# HUM-ASM-001-v0-1.net
KiCad netlist of a schematic drawn in EAGLE
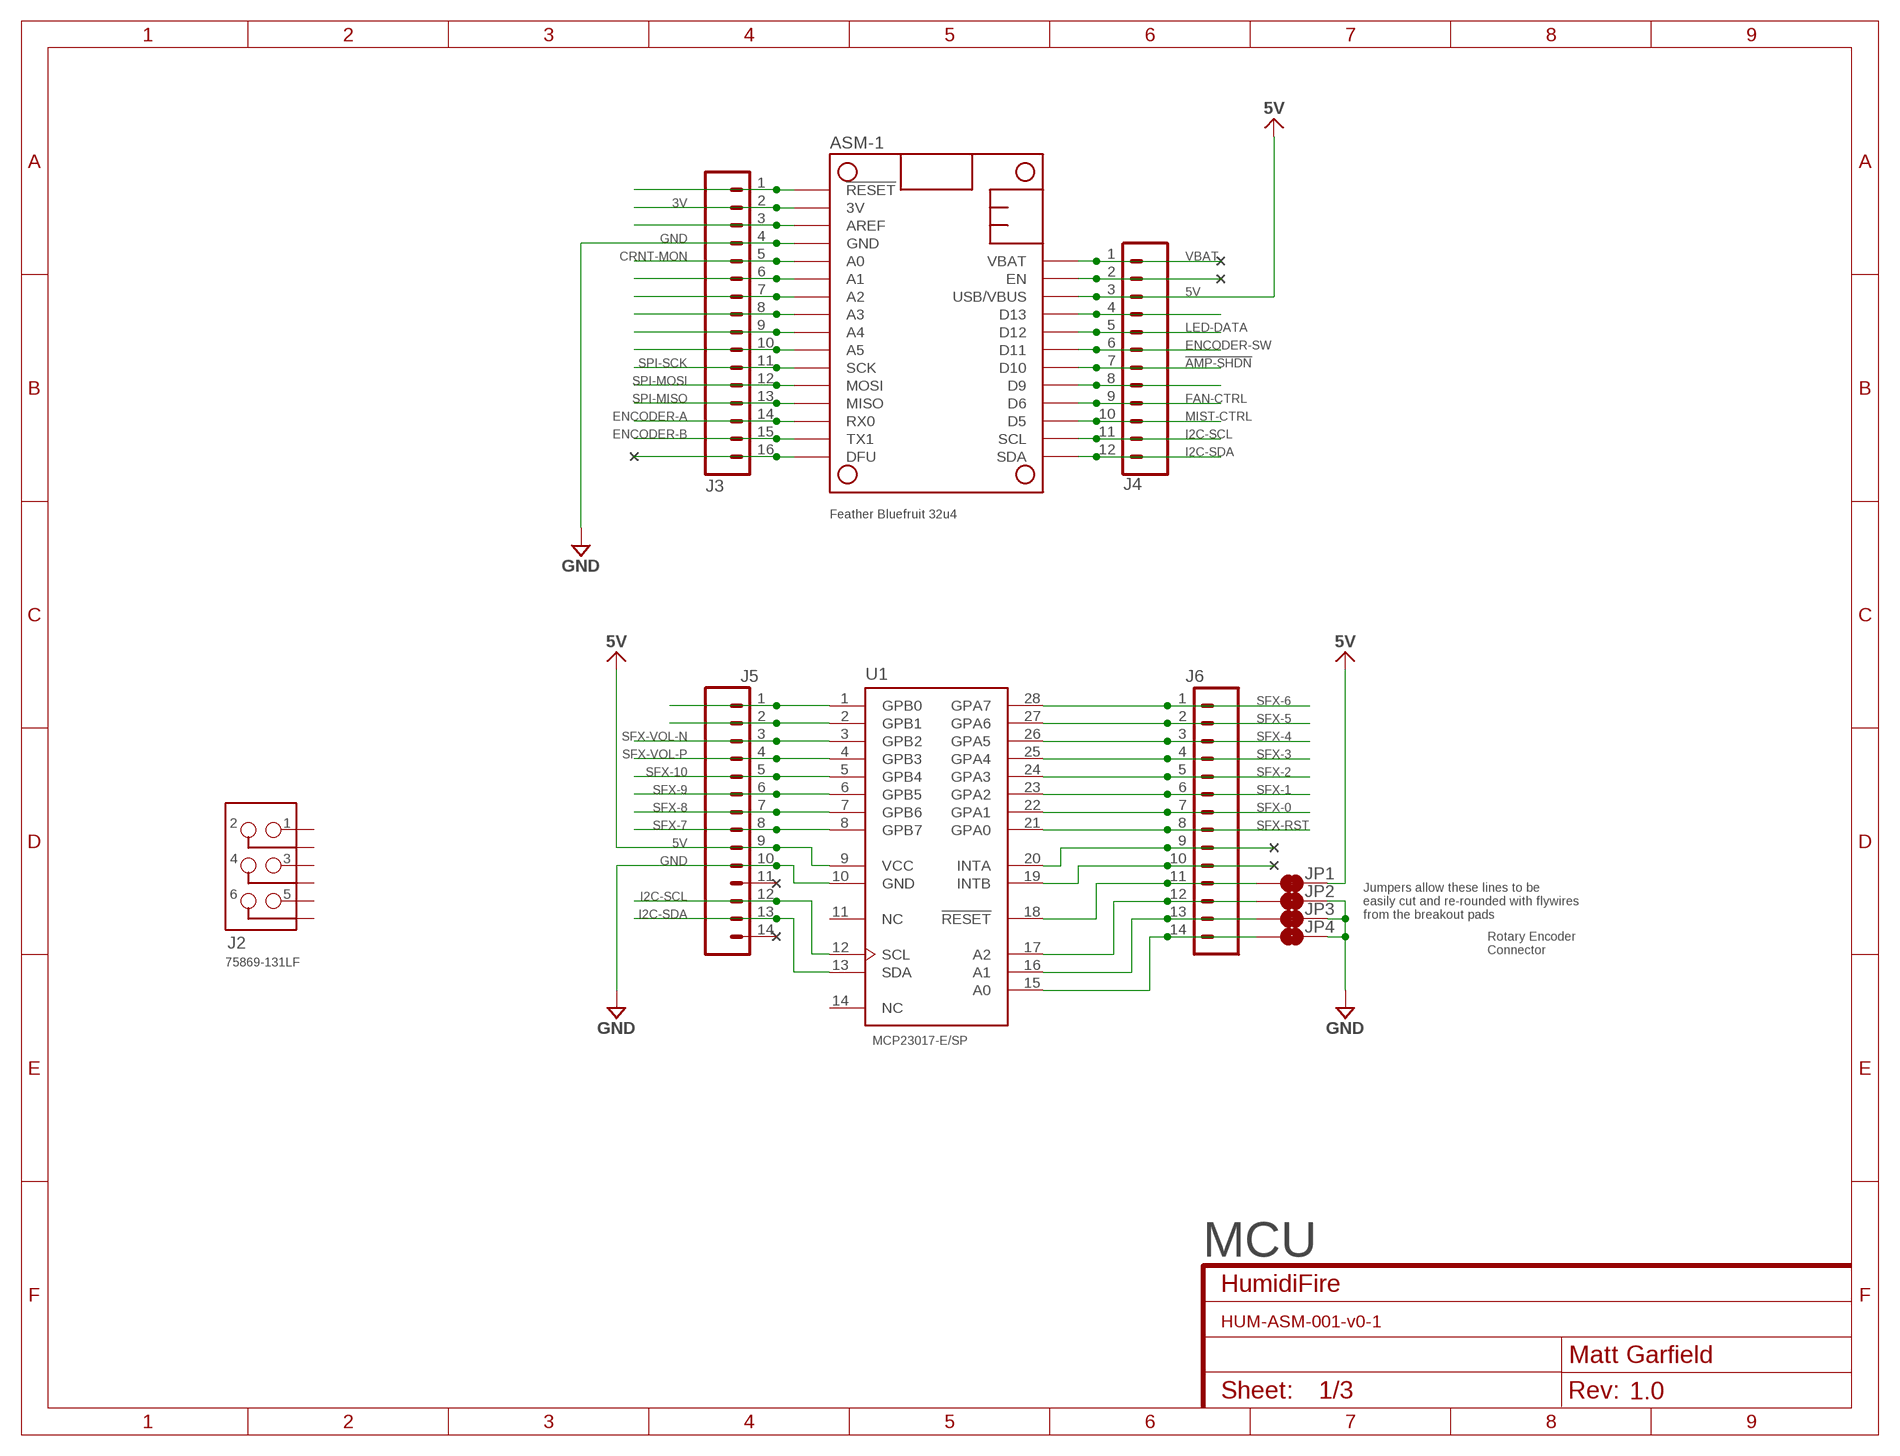
[diagram p0: schematic, sheet 1]
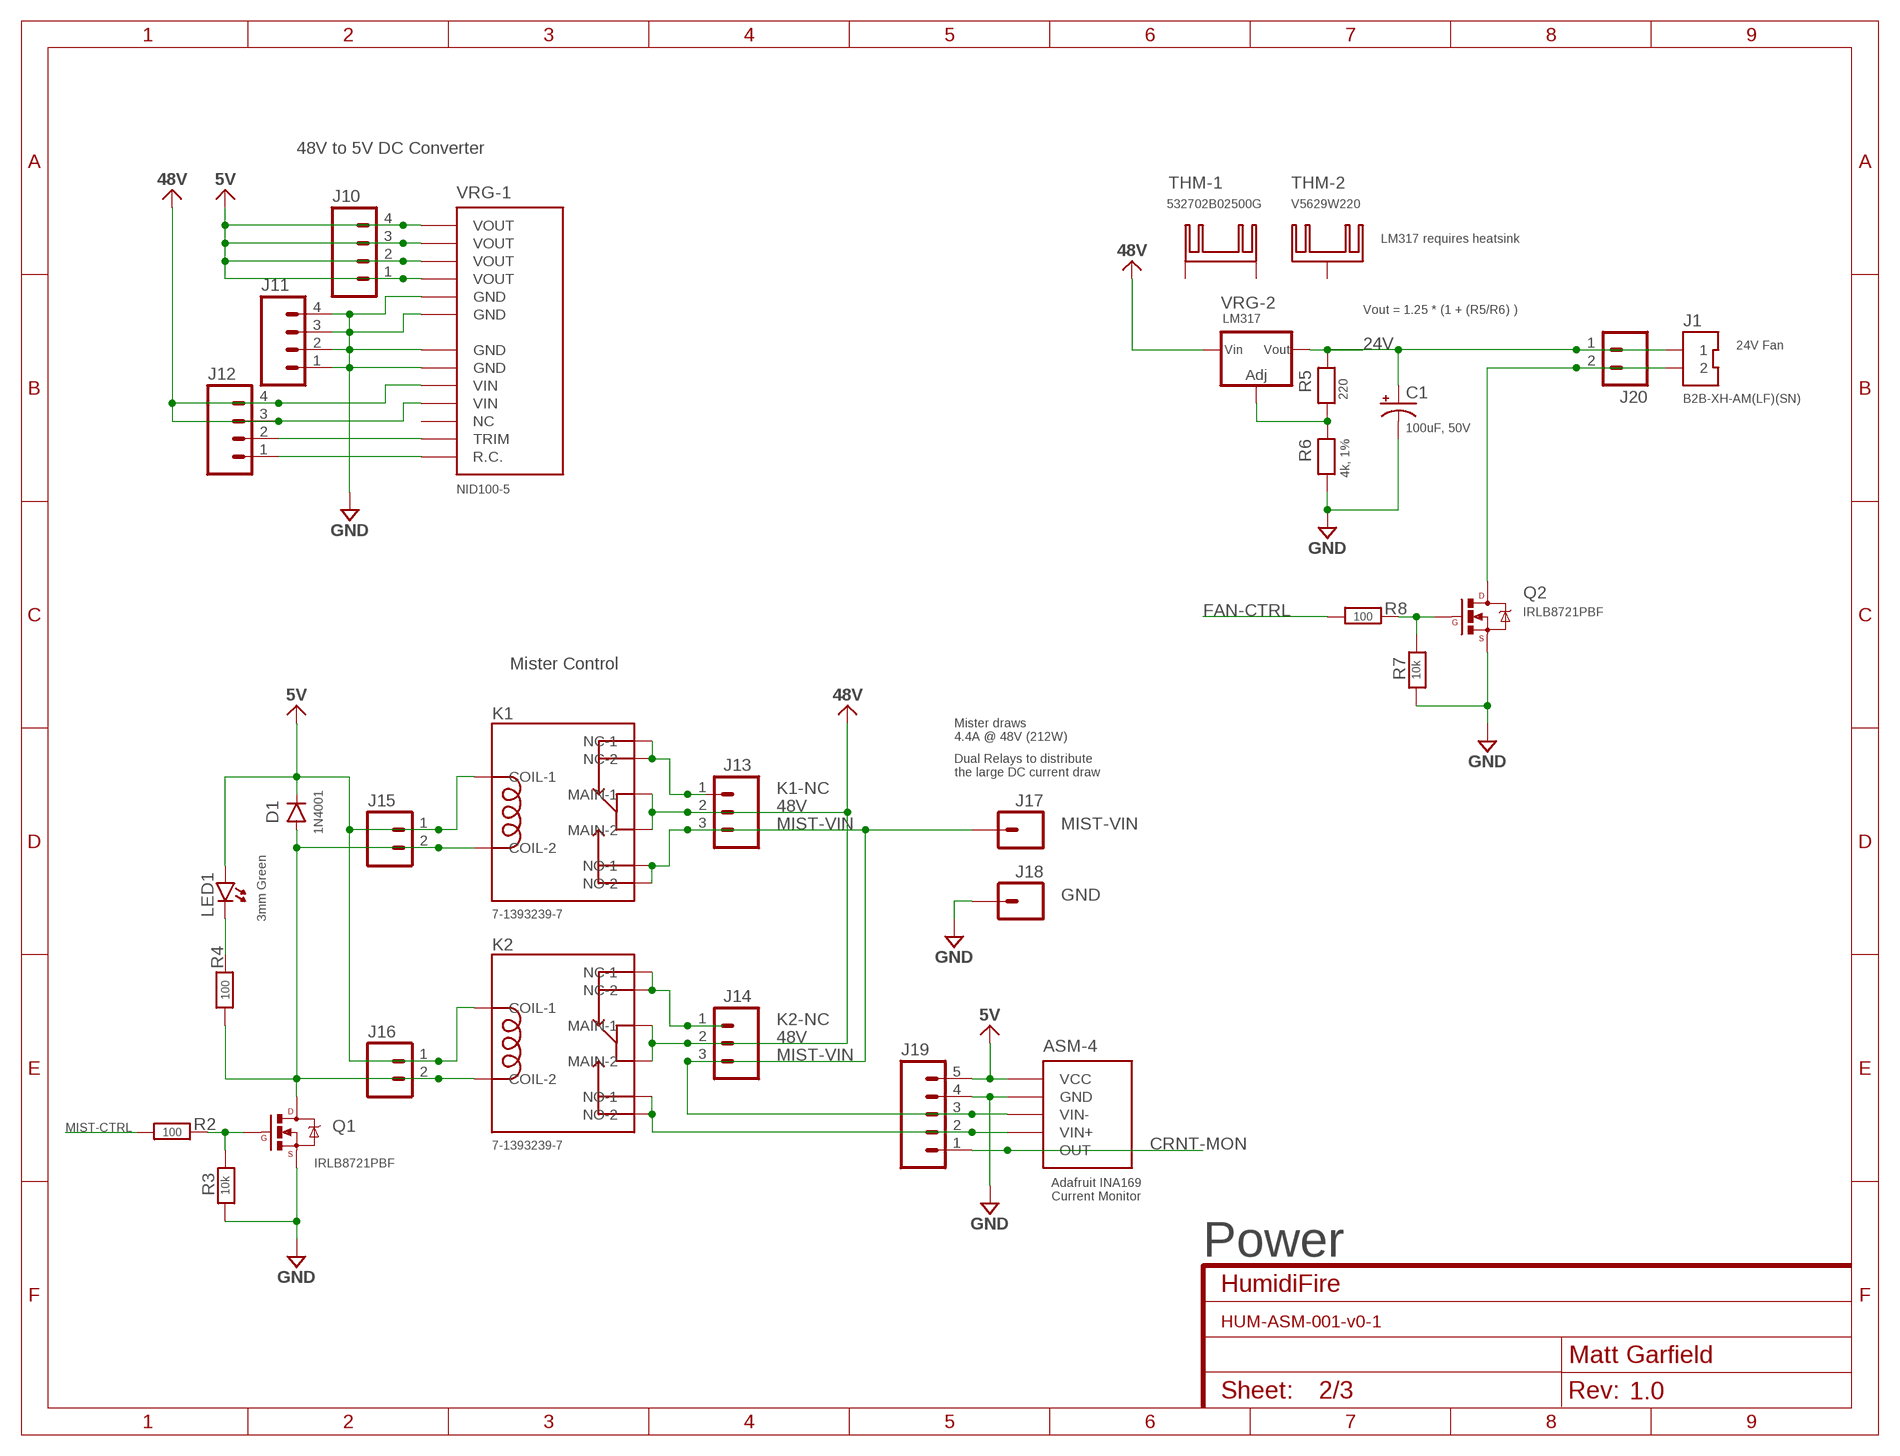
[diagram p1: schematic, sheet 2]
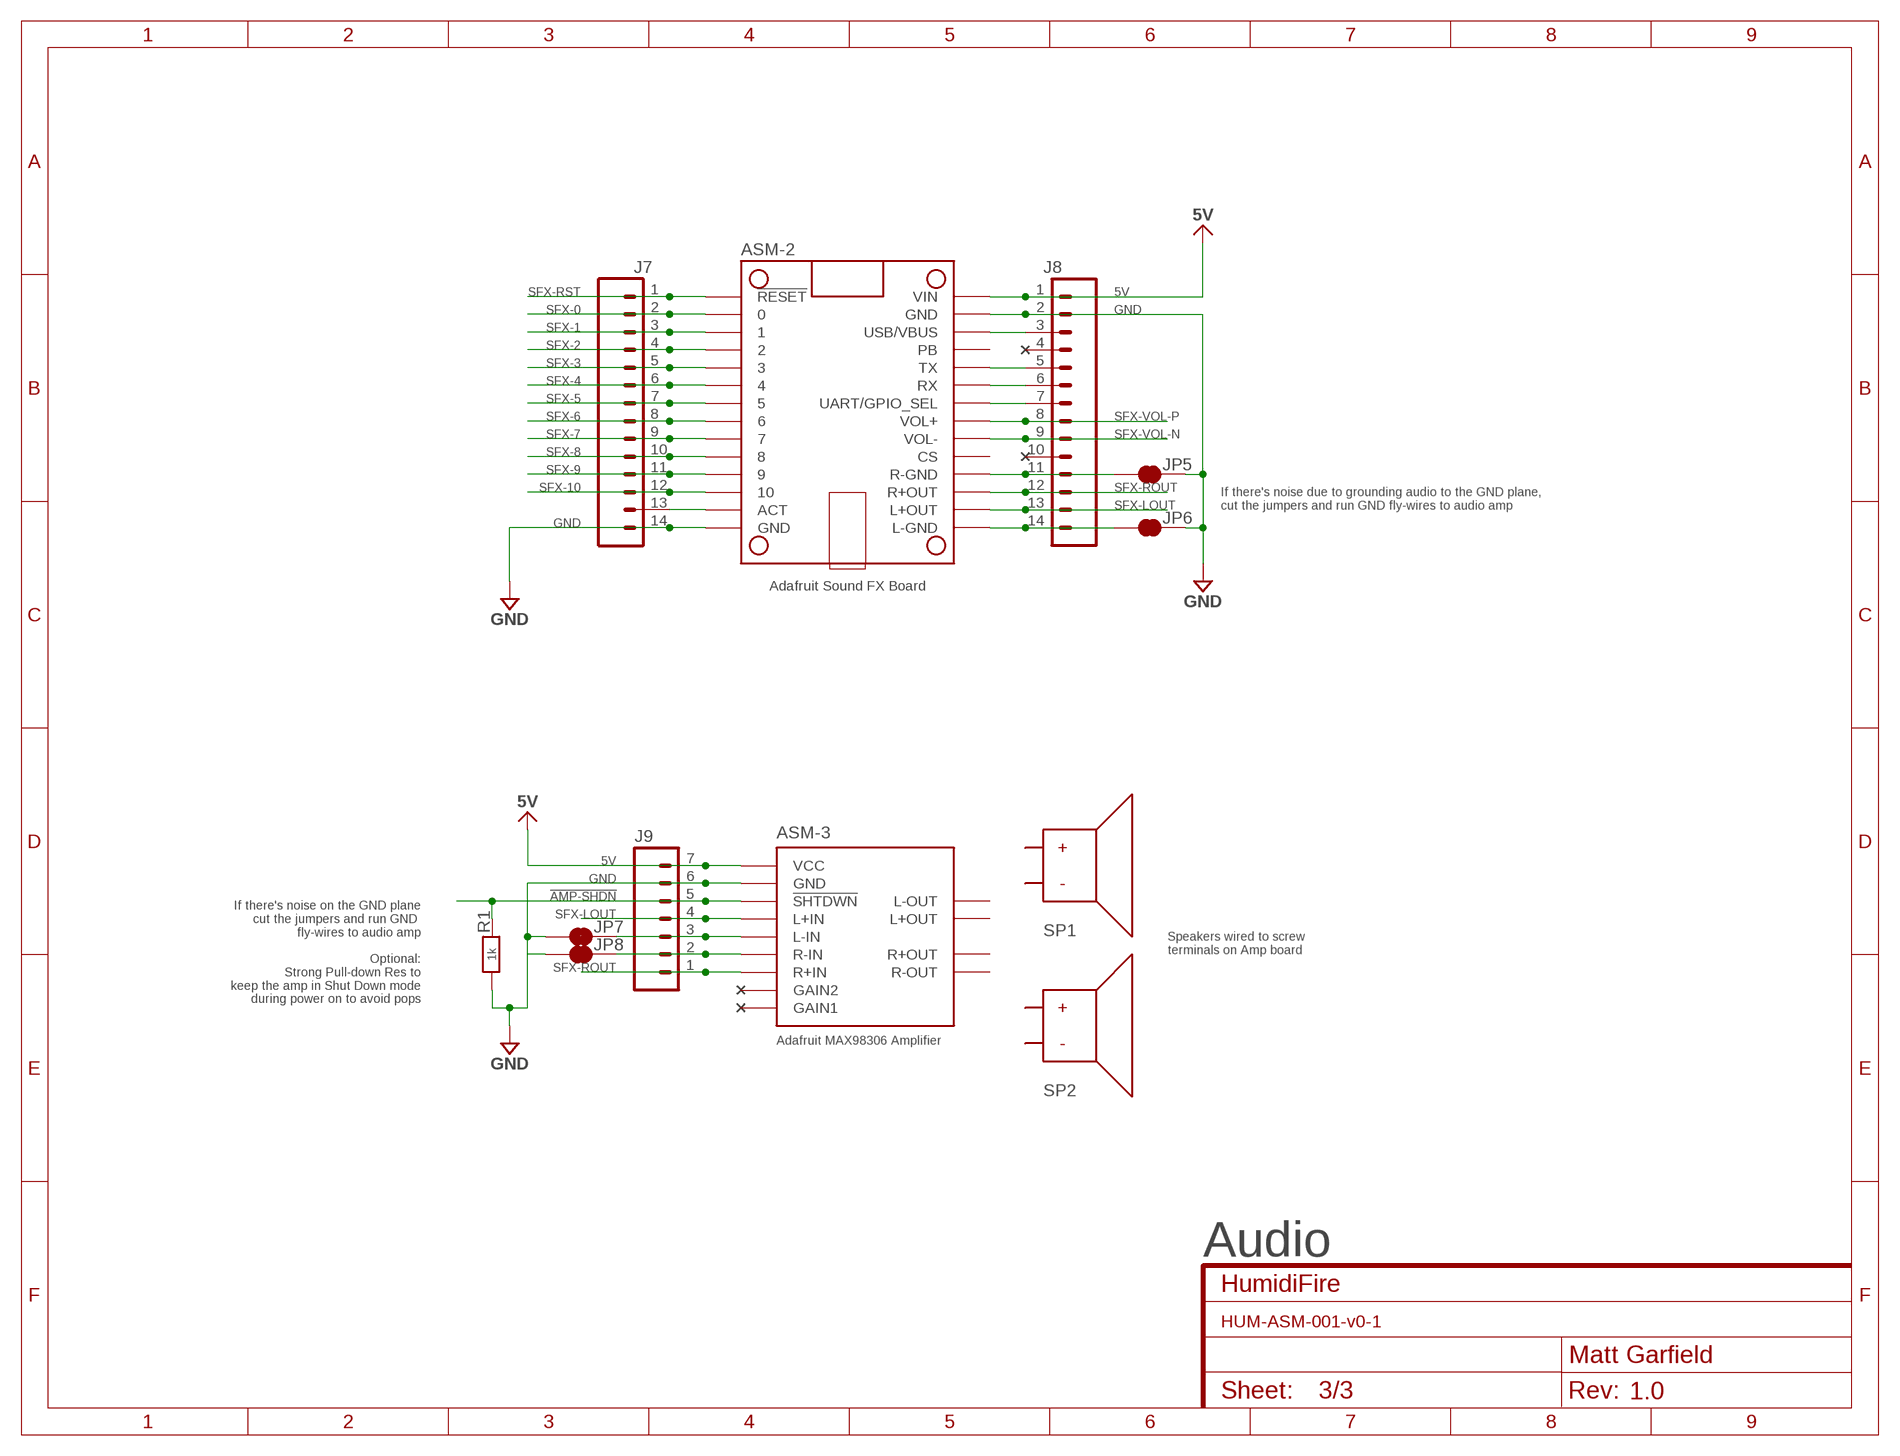
[diagram p2: schematic, sheet 3]

(export (version "E")
  (design (tool "Eeschema 10.0.6"))
  (components
    (comp (ref "ASM-1")
      (value "Feather Bluefruit 32u4")
      (footprint "eagle-import:ASM_ADAFRUIT_FEATHER_BLUEFRUIT")
      (libsource (lib "eagle-import") (part "ASM_ADAFRUIT_FEATHER_BLUEFRUIT"))
    )
    (comp (ref "J2")
      (value "75869-131LF")
      (footprint "eagle-import:2X3-SHROUDED")
      (libsource (lib "eagle-import") (part "CON_HEADER_2X3SHROUD"))
    )
    (comp (ref "J3")
      (value "CON_HEADER_1X16-1X16_NO_SILK")
      (footprint "eagle-import:1X16_NO_SILK")
      (libsource (lib "eagle-import") (part "CON_HEADER_1X16-1X16_NO_SILK"))
    )
    (comp (ref "J4")
      (value "CON_HEADER_1X12_NO_SILK")
      (footprint "eagle-import:1X12_NO_SILK")
      (libsource (lib "eagle-import") (part "CON_HEADER_1X12_NO_SILK"))
    )
    (comp (ref "J5")
      (value "CON_HEADER_1X14")
      (footprint "eagle-import:1X14_NO_SILK")
      (libsource (lib "eagle-import") (part "CON_HEADER_1X14"))
    )
    (comp (ref "J6")
      (value "CON_HEADER_1X14")
      (footprint "eagle-import:1X14_NO_SILK")
      (libsource (lib "eagle-import") (part "CON_HEADER_1X14"))
    )
    (comp (ref "JP1")
      (value "CON_JUMPER_PAD-2-NC_BY_TRACE")
      (footprint "eagle-import:PAD-JUMPER-2-NC_BY_TRACE_YES_SILK")
      (libsource (lib "eagle-import") (part "CON_JUMPER_PAD-2-NC_BY_TRACE"))
    )
    (comp (ref "JP2")
      (value "CON_JUMPER_PAD-2-NC_BY_TRACE")
      (footprint "eagle-import:PAD-JUMPER-2-NC_BY_TRACE_YES_SILK")
      (libsource (lib "eagle-import") (part "CON_JUMPER_PAD-2-NC_BY_TRACE"))
    )
    (comp (ref "JP3")
      (value "CON_JUMPER_PAD-2-NC_BY_TRACE")
      (footprint "eagle-import:PAD-JUMPER-2-NC_BY_TRACE_YES_SILK")
      (libsource (lib "eagle-import") (part "CON_JUMPER_PAD-2-NC_BY_TRACE"))
    )
    (comp (ref "JP4")
      (value "CON_JUMPER_PAD-2-NC_BY_TRACE")
      (footprint "eagle-import:PAD-JUMPER-2-NC_BY_TRACE_YES_SILK")
      (libsource (lib "eagle-import") (part "CON_JUMPER_PAD-2-NC_BY_TRACE"))
    )
    (comp (ref "U1")
      (value "MCP23017-E/SP")
      (footprint "eagle-import:DIP787W45P254L3556H508Q28")
      (fields (field (name "DIGI-KEY_PART_NUMBER") "MCP23017-E/SP-ND") (field (name "MF") "Microchip"))
      (libsource (lib "eagle-import") (part "IIC_MCP23017-E/SP"))
    )
    (comp (ref "ASM-2")
      (value "ASM_ADAFRUIT_SOUND_FX_BOARD")
      (footprint "eagle-import:ASM_ADAFRUIT_SOUND_FX_BOARD")
      (libsource (lib "eagle-import") (part "ASM_ADAFRUIT_SOUND_FX_BOARD"))
    )
    (comp (ref "ASM-3")
      (value "ASM_ADAFRUIT_MAX98306_AMP")
      (footprint "eagle-import:ASM_ADAFRUIT_MAX98306_AMP_MOUNTING_HOLES")
      (libsource (lib "eagle-import") (part "ASM_ADAFRUIT_MAX98306_AMP"))
    )
    (comp (ref "J7")
      (value "CON_HEADER_1X14")
      (footprint "eagle-import:1X14_NO_SILK")
      (libsource (lib "eagle-import") (part "CON_HEADER_1X14"))
    )
    (comp (ref "J8")
      (value "CON_HEADER_1X14")
      (footprint "eagle-import:1X14_NO_SILK")
      (libsource (lib "eagle-import") (part "CON_HEADER_1X14"))
    )
    (comp (ref "J9")
      (value "CON_HEADER_1X7NO_SILK")
      (footprint "eagle-import:1X07_NO_SILK")
      (libsource (lib "eagle-import") (part "CON_HEADER_1X7NO_SILK"))
    )
    (comp (ref "JP5")
      (value "CON_JUMPER_PAD-2-NC_BY_TRACE")
      (footprint "eagle-import:PAD-JUMPER-2-NC_BY_TRACE_YES_SILK")
      (libsource (lib "eagle-import") (part "CON_JUMPER_PAD-2-NC_BY_TRACE"))
    )
    (comp (ref "JP6")
      (value "CON_JUMPER_PAD-2-NC_BY_TRACE")
      (footprint "eagle-import:PAD-JUMPER-2-NC_BY_TRACE_YES_SILK")
      (libsource (lib "eagle-import") (part "CON_JUMPER_PAD-2-NC_BY_TRACE"))
    )
    (comp (ref "JP7")
      (value "CON_JUMPER_PAD-2-NC_BY_TRACE")
      (footprint "eagle-import:PAD-JUMPER-2-NC_BY_TRACE_YES_SILK")
      (libsource (lib "eagle-import") (part "CON_JUMPER_PAD-2-NC_BY_TRACE"))
    )
    (comp (ref "JP8")
      (value "CON_JUMPER_PAD-2-NC_BY_TRACE")
      (footprint "eagle-import:PAD-JUMPER-2-NC_BY_TRACE_YES_SILK")
      (libsource (lib "eagle-import") (part "CON_JUMPER_PAD-2-NC_BY_TRACE"))
    )
    (comp (ref "R1")
      (value "1k")
      (footprint "eagle-import:AXIAL-0.4")
      (libsource (lib "eagle-import") (part "RES_RESISTOR-PTH-1/4W"))
    )
    (comp (ref "ASM-4")
      (value "ASM_ADAFRUIT_INA169")
      (footprint "eagle-import:ASM_ADAFRUIT_INA169_MOUNTING_HOLES")
      (libsource (lib "eagle-import") (part "ASM_ADAFRUIT_INA169"))
    )
    (comp (ref "C1")
      (value "100uF, 50V")
      (footprint "eagle-import:CAP_E-035X080")
      (libsource (lib "eagle-import") (part "CAP_THT_POL-E-035X080MM"))
    )
    (comp (ref "D1")
      (value "1N4001")
      (footprint "eagle-import:DIODE-1N4001")
      (libsource (lib "eagle-import") (part "DIO_DIODEPTH"))
    )
    (comp (ref "J1")
      (value "B2B-XH-AM(LF)(SN)")
      (footprint "eagle-import:JST-2-PTH-VERT_XH")
      (libsource (lib "eagle-import") (part "CON_JST_2-PIN_B2B-XH-AM"))
    )
    (comp (ref "J10")
      (value "CON_HEADER_1X4NO_SILK_ALL_ROUND")
      (footprint "eagle-import:1X04_NO_SILK_ALL_ROUND")
      (libsource (lib "eagle-import") (part "CON_HEADER_1X4NO_SILK_ALL_ROUND"))
    )
    (comp (ref "J11")
      (value "CON_HEADER_1X4NO_SILK_ALL_ROUND")
      (footprint "eagle-import:1X04_NO_SILK_ALL_ROUND")
      (libsource (lib "eagle-import") (part "CON_HEADER_1X4NO_SILK_ALL_ROUND"))
    )
    (comp (ref "J12")
      (value "CON_HEADER_1X4NO_SILK_ALL_ROUND")
      (footprint "eagle-import:1X04_NO_SILK_ALL_ROUND")
      (libsource (lib "eagle-import") (part "CON_HEADER_1X4NO_SILK_ALL_ROUND"))
    )
    (comp (ref "J13")
      (value "CON_HEADER_1X31X03_NO_SILK")
      (footprint "eagle-import:1X03_NO_SILK")
      (libsource (lib "eagle-import") (part "CON_HEADER_1X31X03_NO_SILK"))
    )
    (comp (ref "J14")
      (value "CON_HEADER_1X31X03_NO_SILK")
      (footprint "eagle-import:1X03_NO_SILK")
      (libsource (lib "eagle-import") (part "CON_HEADER_1X31X03_NO_SILK"))
    )
    (comp (ref "J15")
      (value "CON_HEADER_1X21X02_NO_SILK")
      (footprint "eagle-import:1X02_NO_SILK")
      (libsource (lib "eagle-import") (part "CON_HEADER_1X21X02_NO_SILK"))
    )
    (comp (ref "J16")
      (value "CON_HEADER_1X21X02_NO_SILK")
      (footprint "eagle-import:1X02_NO_SILK")
      (libsource (lib "eagle-import") (part "CON_HEADER_1X21X02_NO_SILK"))
    )
    (comp (ref "J17")
      (value "CON_HEADER_1X1-QC_TAB_121786-1")
      (footprint "eagle-import:TE_1217861-1")
      (libsource (lib "eagle-import") (part "CON_HEADER_1X1-QC_TAB_121786-1"))
    )
    (comp (ref "J18")
      (value "CON_HEADER_1X1-QC_TAB_121786-1")
      (footprint "eagle-import:TE_1217861-1")
      (libsource (lib "eagle-import") (part "CON_HEADER_1X1-QC_TAB_121786-1"))
    )
    (comp (ref "J19")
      (value "CON_HEADER_1X5NO_SILK")
      (footprint "eagle-import:1X05_NO_SILK")
      (libsource (lib "eagle-import") (part "CON_HEADER_1X5NO_SILK"))
    )
    (comp (ref "J20")
      (value "CON_HEADER_1X21X02_NO_SILK")
      (footprint "eagle-import:1X02_NO_SILK")
      (libsource (lib "eagle-import") (part "CON_HEADER_1X21X02_NO_SILK"))
    )
    (comp (ref "K1")
      (value "7-1393239-7")
      (footprint "eagle-import:RELAY_TE_7-1393239-7")
      (libsource (lib "eagle-import") (part "EMD_RELAY_SPDT_8-PIN_TE_7-1393239-7"))
    )
    (comp (ref "K2")
      (value "7-1393239-7")
      (footprint "eagle-import:RELAY_TE_7-1393239-7")
      (libsource (lib "eagle-import") (part "EMD_RELAY_SPDT_8-PIN_TE_7-1393239-7"))
    )
    (comp (ref "LED1")
      (value "3mm Green")
      (footprint "eagle-import:LED3MM")
      (libsource (lib "eagle-import") (part "LED_THT-3MM"))
    )
    (comp (ref "Q1")
      (value "IRLB8721PBF")
      (footprint "eagle-import:TO-220-VERTICAL")
      (libsource (lib "eagle-import") (part "TRN_MOSFET-N_TO-220_VERTICAL"))
    )
    (comp (ref "Q2")
      (value "IRLB8721PBF")
      (footprint "eagle-import:TO-220-VERTICAL")
      (libsource (lib "eagle-import") (part "TRN_MOSFET-N_TO-220_VERTICAL"))
    )
    (comp (ref "R2")
      (value "100")
      (footprint "eagle-import:AXIAL-0.4")
      (libsource (lib "eagle-import") (part "RES_RESISTOR-PTH-1/4W"))
    )
    (comp (ref "R3")
      (value "10k")
      (footprint "eagle-import:AXIAL-0.4")
      (libsource (lib "eagle-import") (part "RES_RESISTOR-PTH-1/4W"))
    )
    (comp (ref "R4")
      (value "100")
      (footprint "eagle-import:AXIAL-0.4")
      (libsource (lib "eagle-import") (part "RES_RESISTOR-PTH-1/4W"))
    )
    (comp (ref "R5")
      (value "220")
      (footprint "eagle-import:AXIAL-0.4")
      (libsource (lib "eagle-import") (part "RES_RESISTOR-PTH-1/4W"))
    )
    (comp (ref "R6")
      (value "4k, 1%")
      (footprint "eagle-import:AXIAL-0.4")
      (libsource (lib "eagle-import") (part "RES_RESISTOR-PTH-1/4W"))
    )
    (comp (ref "R7")
      (value "10k")
      (footprint "eagle-import:AXIAL-0.4")
      (libsource (lib "eagle-import") (part "RES_RESISTOR-PTH-1/4W"))
    )
    (comp (ref "R8")
      (value "100")
      (footprint "eagle-import:AXIAL-0.4")
      (libsource (lib "eagle-import") (part "RES_RESISTOR-PTH-1/4W"))
    )
    (comp (ref "THM-1")
      (value "532702B02500G")
      (footprint "eagle-import:HEATSINK_AAVID_532XX")
      (libsource (lib "eagle-import") (part "THM_HEATSINK_2-PIN"))
    )
    (comp (ref "THM-2")
      (value "V5629W220")
      (footprint "eagle-import:SK95-2M3")
      (libsource (lib "eagle-import") (part "THM_HEATSINK_1-PIN"))
    )
    (comp (ref "VRG-1")
      (value "NID100-5")
      (footprint "eagle-import:VRG_NID100-X")
      (libsource (lib "eagle-import") (part "VRG_NID100"))
    )
    (comp (ref "VRG-2")
      (value "LM317")
      (footprint "eagle-import:TO-220-VERTICAL")
      (libsource (lib "eagle-import") (part "VRG_LM317_TO-220_VERTICAL"))
    )
  )
  (nets
    (net (code "1") (name "3V") (class "Default")
      (node (ref "ASM-1") (pin "3V3") (pinfunction "3V_3V3") (pintype "power_in"))
      (node (ref "J3") (pin "2") (pinfunction "2_2") (pintype "passive"))
    )
    (net (code "2") (name "5V") (class "Default")
      (node (ref "ASM-1") (pin "USB/VBUS") (pinfunction "USB/VBUS_USB/VBUS") (pintype "power_in"))
      (node (ref "ASM-2") (pin "28") (pinfunction "VIN_28") (pintype "power_in"))
      (node (ref "ASM-3") (pin "1") (pinfunction "VCC_1") (pintype "power_in"))
      (node (ref "ASM-4") (pin "1") (pinfunction "VCC_1") (pintype "power_in"))
      (node (ref "D1") (pin "C") (pinfunction "C_C") (pintype "passive"))
      (node (ref "J10") (pin "1") (pinfunction "1_1") (pintype "passive"))
      (node (ref "J10") (pin "2") (pinfunction "2_2") (pintype "passive"))
      (node (ref "J10") (pin "3") (pinfunction "3_3") (pintype "passive"))
      (node (ref "J10") (pin "4") (pinfunction "4_4") (pintype "passive"))
      (node (ref "J15") (pin "1") (pinfunction "P1_1") (pintype "passive"))
      (node (ref "J16") (pin "1") (pinfunction "P1_1") (pintype "passive"))
      (node (ref "J19") (pin "5") (pinfunction "5_5") (pintype "passive"))
      (node (ref "J4") (pin "3") (pinfunction "3_3") (pintype "passive"))
      (node (ref "J5") (pin "9") (pinfunction "9_9") (pintype "passive"))
      (node (ref "J8") (pin "1") (pinfunction "1_1") (pintype "passive"))
      (node (ref "J9") (pin "7") (pinfunction "7_7") (pintype "passive"))
      (node (ref "JP1") (pin "2") (pinfunction "2_2") (pintype "passive"))
      (node (ref "K1") (pin "COIL-1") (pinfunction "COIL-1_COIL-1") (pintype "bidirectional"))
      (node (ref "K2") (pin "COIL-1") (pinfunction "COIL-1_COIL-1") (pintype "bidirectional"))
      (node (ref "LED1") (pin "A") (pinfunction "A_A") (pintype "passive"))
      (node (ref "U1") (pin "9") (pinfunction "VCC_9") (pintype "power_in"))
      (node (ref "VRG-1") (pin "P$1") (pinfunction "VOUT_P$1") (pintype "power_in"))
      (node (ref "VRG-1") (pin "P$2") (pinfunction "VOUT_P$2") (pintype "power_in"))
      (node (ref "VRG-1") (pin "P$3") (pinfunction "VOUT_P$3") (pintype "power_in"))
      (node (ref "VRG-1") (pin "P$4") (pinfunction "VOUT_P$4") (pintype "power_in"))
    )
    (net (code "3") (name "24V") (class "Default")
      (node (ref "C1") (pin "+") (pinfunction "+_+") (pintype "passive"))
      (node (ref "J1") (pin "1") (pinfunction "1_1") (pintype "bidirectional"))
      (node (ref "J20") (pin "1") (pinfunction "P1_1") (pintype "passive"))
      (node (ref "R5") (pin "P$2") (pinfunction "P2_P$2") (pintype "passive"))
      (node (ref "VRG-2") (pin "P2") (pinfunction "VOUT_P2") (pintype "power_in"))
    )
    (net (code "4") (name "48V") (class "Default")
      (node (ref "J12") (pin "3") (pinfunction "3_3") (pintype "passive"))
      (node (ref "J12") (pin "4") (pinfunction "4_4") (pintype "passive"))
      (node (ref "J13") (pin "2") (pinfunction "P2_2") (pintype "passive"))
      (node (ref "J14") (pin "2") (pinfunction "P2_2") (pintype "passive"))
      (node (ref "K1") (pin "MAIN-1") (pinfunction "MAIN-1_MAIN-1") (pintype "bidirectional"))
      (node (ref "K1") (pin "MAIN-2") (pinfunction "MAIN-2_MAIN-2") (pintype "bidirectional"))
      (node (ref "K2") (pin "MAIN-1") (pinfunction "MAIN-1_MAIN-1") (pintype "bidirectional"))
      (node (ref "K2") (pin "MAIN-2") (pinfunction "MAIN-2_MAIN-2") (pintype "bidirectional"))
      (node (ref "VRG-1") (pin "P$10") (pinfunction "VIN_P$10") (pintype "power_in"))
      (node (ref "VRG-1") (pin "P$9") (pinfunction "VIN_P$9") (pintype "power_in"))
      (node (ref "VRG-2") (pin "P3") (pinfunction "VIN_P3") (pintype "power_in"))
    )
    (net (code "5") (name "CRNT-MON") (class "Default")
      (node (ref "ASM-1") (pin "A0") (pinfunction "A0_A0") (pintype "bidirectional"))
      (node (ref "ASM-4") (pin "5") (pinfunction "OUT_5") (pintype "output"))
      (node (ref "J19") (pin "1") (pinfunction "1_1") (pintype "passive"))
      (node (ref "J3") (pin "5") (pinfunction "5_5") (pintype "passive"))
    )
    (net (code "6") (name "ENCODER-A") (class "Default")
      (node (ref "ASM-1") (pin "RX0") (pinfunction "RX0_RX0") (pintype "bidirectional"))
      (node (ref "J3") (pin "14") (pinfunction "14_14") (pintype "passive"))
    )
    (net (code "7") (name "ENCODER-B") (class "Default")
      (node (ref "ASM-1") (pin "TX1") (pinfunction "TX1_TX1") (pintype "bidirectional"))
      (node (ref "J3") (pin "15") (pinfunction "15_15") (pintype "passive"))
    )
    (net (code "8") (name "ENCODER-SW") (class "Default")
      (node (ref "ASM-1") (pin "D11") (pinfunction "D11_D11") (pintype "bidirectional"))
      (node (ref "J4") (pin "6") (pinfunction "6_6") (pintype "passive"))
    )
    (net (code "9") (name "FAN-CTRL") (class "Default")
      (node (ref "ASM-1") (pin "D6") (pinfunction "D6_D6") (pintype "bidirectional"))
      (node (ref "J4") (pin "9") (pinfunction "9_9") (pintype "passive"))
      (node (ref "R8") (pin "P$1") (pinfunction "P1_P$1") (pintype "passive"))
    )
    (net (code "10") (name "GND") (class "Default")
      (node (ref "ASM-1") (pin "GND@4") (pinfunction "GND_GND@4") (pintype "power_in"))
      (node (ref "ASM-2") (pin "14") (pinfunction "GND_14") (pintype "power_in"))
      (node (ref "ASM-2") (pin "27") (pinfunction "GND_27") (pintype "power_in"))
      (node (ref "ASM-3") (pin "2") (pinfunction "GND_2") (pintype "power_in"))
      (node (ref "ASM-4") (pin "2") (pinfunction "GND_2") (pintype "power_in"))
      (node (ref "C1") (pin "-") (pinfunction "-_-") (pintype "passive"))
      (node (ref "J11") (pin "1") (pinfunction "1_1") (pintype "passive"))
      (node (ref "J11") (pin "2") (pinfunction "2_2") (pintype "passive"))
      (node (ref "J11") (pin "3") (pinfunction "3_3") (pintype "passive"))
      (node (ref "J11") (pin "4") (pinfunction "4_4") (pintype "passive"))
      (node (ref "J18") (pin "1") (pinfunction "1_1") (pintype "passive"))
      (node (ref "J18") (pin "2") (pinfunction "1_2") (pintype "passive"))
      (node (ref "J19") (pin "4") (pinfunction "4_4") (pintype "passive"))
      (node (ref "J3") (pin "4") (pinfunction "4_4") (pintype "passive"))
      (node (ref "J5") (pin "10") (pinfunction "10_10") (pintype "passive"))
      (node (ref "J7") (pin "14") (pinfunction "14_14") (pintype "passive"))
      (node (ref "J8") (pin "2") (pinfunction "2_2") (pintype "passive"))
      (node (ref "J9") (pin "6") (pinfunction "6_6") (pintype "passive"))
      (node (ref "JP2") (pin "2") (pinfunction "2_2") (pintype "passive"))
      (node (ref "JP3") (pin "2") (pinfunction "2_2") (pintype "passive"))
      (node (ref "JP4") (pin "2") (pinfunction "2_2") (pintype "passive"))
      (node (ref "JP5") (pin "2") (pinfunction "2_2") (pintype "passive"))
      (node (ref "JP6") (pin "2") (pinfunction "2_2") (pintype "passive"))
      (node (ref "JP7") (pin "1") (pinfunction "1_1") (pintype "passive"))
      (node (ref "JP8") (pin "1") (pinfunction "1_1") (pintype "passive"))
      (node (ref "Q1") (pin "P3") (pinfunction "S_P3") (pintype "passive"))
      (node (ref "Q2") (pin "P3") (pinfunction "S_P3") (pintype "passive"))
      (node (ref "R1") (pin "P$1") (pinfunction "P1_P$1") (pintype "passive"))
      (node (ref "R3") (pin "P$2") (pinfunction "P2_P$2") (pintype "passive"))
      (node (ref "R6") (pin "P$1") (pinfunction "P1_P$1") (pintype "passive"))
      (node (ref "R7") (pin "P$2") (pinfunction "P2_P$2") (pintype "passive"))
      (node (ref "U1") (pin "10") (pinfunction "GND_10") (pintype "power_in"))
      (node (ref "VRG-1") (pin "P$5") (pinfunction "GND_P$5") (pintype "power_in"))
      (node (ref "VRG-1") (pin "P$6") (pinfunction "GND_P$6") (pintype "power_in"))
      (node (ref "VRG-1") (pin "P$7") (pinfunction "GND_P$7") (pintype "power_in"))
      (node (ref "VRG-1") (pin "P$8") (pinfunction "GND_P$8") (pintype "power_in"))
    )
    (net (code "11") (name "I2C-SCL") (class "Default")
      (node (ref "ASM-1") (pin "SCL") (pinfunction "SCL_SCL") (pintype "bidirectional"))
      (node (ref "J4") (pin "11") (pinfunction "11_11") (pintype "passive"))
      (node (ref "J5") (pin "12") (pinfunction "12_12") (pintype "passive"))
      (node (ref "U1") (pin "12") (pinfunction "SCL_12") (pintype "input"))
    )
    (net (code "12") (name "I2C-SDA") (class "Default")
      (node (ref "ASM-1") (pin "SDA") (pinfunction "SDA_SDA") (pintype "bidirectional"))
      (node (ref "J4") (pin "12") (pinfunction "12_12") (pintype "passive"))
      (node (ref "J5") (pin "13") (pinfunction "13_13") (pintype "passive"))
      (node (ref "U1") (pin "13") (pinfunction "SDA_13") (pintype "bidirectional"))
    )
    (net (code "13") (name "K1-NC") (class "Default")
      (node (ref "J13") (pin "1") (pinfunction "P1_1") (pintype "passive"))
      (node (ref "K1") (pin "NC-1") (pinfunction "NC-1_NC-1") (pintype "bidirectional"))
      (node (ref "K1") (pin "NC-2") (pinfunction "NC-2_NC-2") (pintype "bidirectional"))
    )
    (net (code "14") (name "K2-NC") (class "Default")
      (node (ref "J14") (pin "1") (pinfunction "P1_1") (pintype "passive"))
      (node (ref "K2") (pin "NC-1") (pinfunction "NC-1_NC-1") (pintype "bidirectional"))
      (node (ref "K2") (pin "NC-2") (pinfunction "NC-2_NC-2") (pintype "bidirectional"))
    )
    (net (code "15") (name "LED-DATA") (class "Default")
      (node (ref "ASM-1") (pin "D12") (pinfunction "D12_D12") (pintype "bidirectional"))
      (node (ref "J4") (pin "5") (pinfunction "5_5") (pintype "passive"))
    )
    (net (code "16") (name "MIST-CTRL") (class "Default")
      (node (ref "ASM-1") (pin "D5") (pinfunction "D5_D5") (pintype "bidirectional"))
      (node (ref "J4") (pin "10") (pinfunction "10_10") (pintype "passive"))
      (node (ref "R2") (pin "P$1") (pinfunction "P1_P$1") (pintype "passive"))
    )
    (net (code "17") (name "MIST-VIN") (class "Default")
      (node (ref "ASM-4") (pin "3") (pinfunction "VIN-_3") (pintype "bidirectional"))
      (node (ref "J13") (pin "3") (pinfunction "P3_3") (pintype "passive"))
      (node (ref "J14") (pin "3") (pinfunction "P3_3") (pintype "passive"))
      (node (ref "J17") (pin "1") (pinfunction "1_1") (pintype "passive"))
      (node (ref "J17") (pin "2") (pinfunction "1_2") (pintype "passive"))
      (node (ref "J19") (pin "3") (pinfunction "3_3") (pintype "passive"))
      (node (ref "K1") (pin "NO-1") (pinfunction "NO-1_NO-1") (pintype "bidirectional"))
      (node (ref "K1") (pin "NO-2") (pinfunction "NO-2_NO-2") (pintype "bidirectional"))
    )
    (net (code "18") (name "Net-(ASM-1-PadA1)") (class "Default")
      (node (ref "ASM-1") (pin "A1") (pinfunction "A1_A1") (pintype "bidirectional"))
      (node (ref "J3") (pin "6") (pinfunction "6_6") (pintype "passive"))
    )
    (net (code "19") (name "Net-(ASM-1-PadA2)") (class "Default")
      (node (ref "ASM-1") (pin "A2") (pinfunction "A2_A2") (pintype "bidirectional"))
      (node (ref "J3") (pin "7") (pinfunction "7_7") (pintype "passive"))
    )
    (net (code "20") (name "Net-(ASM-1-PadA3)") (class "Default")
      (node (ref "ASM-1") (pin "A3") (pinfunction "A3_A3") (pintype "bidirectional"))
      (node (ref "J3") (pin "8") (pinfunction "8_8") (pintype "passive"))
    )
    (net (code "21") (name "Net-(ASM-1-PadA4)") (class "Default")
      (node (ref "ASM-1") (pin "A4") (pinfunction "A4_A4") (pintype "bidirectional"))
      (node (ref "J3") (pin "9") (pinfunction "9_9") (pintype "passive"))
    )
    (net (code "22") (name "Net-(ASM-1-PadA5)") (class "Default")
      (node (ref "ASM-1") (pin "A5") (pinfunction "A5_A5") (pintype "bidirectional"))
      (node (ref "J3") (pin "10") (pinfunction "10_10") (pintype "passive"))
    )
    (net (code "23") (name "Net-(ASM-1-PadAREF)") (class "Default")
      (node (ref "ASM-1") (pin "AREF") (pinfunction "AREF_AREF") (pintype "passive"))
      (node (ref "J3") (pin "3") (pinfunction "3_3") (pintype "passive"))
    )
    (net (code "24") (name "Net-(ASM-1-PadD9)") (class "Default")
      (node (ref "ASM-1") (pin "D9") (pinfunction "D9_D9") (pintype "bidirectional"))
      (node (ref "J4") (pin "8") (pinfunction "8_8") (pintype "passive"))
    )
    (net (code "25") (name "Net-(ASM-1-PadD13)") (class "Default")
      (node (ref "ASM-1") (pin "D13") (pinfunction "D13_D13") (pintype "bidirectional"))
      (node (ref "J4") (pin "4") (pinfunction "4_4") (pintype "passive"))
    )
    (net (code "26") (name "Net-(ASM-1-PadDFU)") (class "Default")
      (node (ref "ASM-1") (pin "DFU") (pinfunction "DFU_DFU") (pintype "bidirectional"))
      (node (ref "J3") (pin "16") (pinfunction "16_16") (pintype "passive"))
    )
    (net (code "27") (name "Net-(ASM-1-PadEN)") (class "Default")
      (node (ref "ASM-1") (pin "EN") (pinfunction "EN_EN") (pintype "passive"))
      (node (ref "J4") (pin "2") (pinfunction "2_2") (pintype "passive"))
    )
    (net (code "28") (name "Net-(ASM-1-~{RESET})") (class "Default")
      (node (ref "ASM-1") (pin "!RESET") (pinfunction "~{RESET}_!RESET") (pintype "input"))
      (node (ref "J3") (pin "1") (pinfunction "1_1") (pintype "passive"))
    )
    (net (code "29") (name "Net-(ASM-2-ACT)") (class "Default")
      (node (ref "ASM-2") (pin "13") (pinfunction "ACT_13") (pintype "output"))
      (node (ref "J7") (pin "13") (pinfunction "13_13") (pintype "passive"))
    )
    (net (code "30") (name "Net-(ASM-2-L-GND)") (class "Default")
      (node (ref "ASM-2") (pin "15") (pinfunction "L-GND_15") (pintype "power_in"))
      (node (ref "J8") (pin "14") (pinfunction "14_14") (pintype "passive"))
      (node (ref "JP6") (pin "1") (pinfunction "1_1") (pintype "passive"))
    )
    (net (code "31") (name "Net-(ASM-2-R-GND)") (class "Default")
      (node (ref "ASM-2") (pin "18") (pinfunction "R-GND_18") (pintype "bidirectional"))
      (node (ref "J8") (pin "11") (pinfunction "11_11") (pintype "passive"))
      (node (ref "JP5") (pin "1") (pinfunction "1_1") (pintype "passive"))
    )
    (net (code "32") (name "Net-(ASM-2-RX)") (class "Default")
      (node (ref "ASM-2") (pin "23") (pinfunction "RX_23") (pintype "input"))
      (node (ref "J8") (pin "6") (pinfunction "6_6") (pintype "passive"))
    )
    (net (code "33") (name "Net-(ASM-2-TX)") (class "Default")
      (node (ref "ASM-2") (pin "24") (pinfunction "TX_24") (pintype "output"))
      (node (ref "J8") (pin "5") (pinfunction "5_5") (pintype "passive"))
    )
    (net (code "34") (name "Net-(ASM-2-UART{slash}GPIO_SEL)") (class "Default")
      (node (ref "ASM-2") (pin "22") (pinfunction "UART/GPIO_SEL_22") (pintype "bidirectional"))
      (node (ref "J8") (pin "7") (pinfunction "7_7") (pintype "passive"))
    )
    (net (code "35") (name "Net-(ASM-2-USB{slash}VBUS)") (class "Default")
      (node (ref "ASM-2") (pin "26") (pinfunction "USB/VBUS_26") (pintype "power_in"))
      (node (ref "J8") (pin "3") (pinfunction "3_3") (pintype "passive"))
    )
    (net (code "36") (name "Net-(ASM-3-L-IN)") (class "Default")
      (node (ref "ASM-3") (pin "5") (pinfunction "L-IN_5") (pintype "input"))
      (node (ref "J9") (pin "3") (pinfunction "3_3") (pintype "passive"))
      (node (ref "JP7") (pin "2") (pinfunction "2_2") (pintype "passive"))
    )
    (net (code "37") (name "Net-(ASM-3-R-IN)") (class "Default")
      (node (ref "ASM-3") (pin "6") (pinfunction "R-IN_6") (pintype "input"))
      (node (ref "J9") (pin "2") (pinfunction "2_2") (pintype "passive"))
      (node (ref "JP8") (pin "2") (pinfunction "2_2") (pintype "passive"))
    )
    (net (code "38") (name "Net-(ASM-4-VIN+)") (class "Default")
      (node (ref "ASM-4") (pin "4") (pinfunction "VIN+_4") (pintype "bidirectional"))
      (node (ref "J19") (pin "2") (pinfunction "2_2") (pintype "passive"))
      (node (ref "K2") (pin "NO-1") (pinfunction "NO-1_NO-1") (pintype "bidirectional"))
      (node (ref "K2") (pin "NO-2") (pinfunction "NO-2_NO-2") (pintype "bidirectional"))
    )
    (net (code "39") (name "Net-(J15-P2)") (class "Default")
      (node (ref "D1") (pin "A") (pinfunction "A_A") (pintype "passive"))
      (node (ref "J15") (pin "2") (pinfunction "P2_2") (pintype "passive"))
      (node (ref "J16") (pin "2") (pinfunction "P2_2") (pintype "passive"))
      (node (ref "K1") (pin "COIL-2") (pinfunction "COIL-2_COIL-2") (pintype "bidirectional"))
      (node (ref "K2") (pin "COIL-2") (pinfunction "COIL-2_COIL-2") (pintype "bidirectional"))
      (node (ref "Q1") (pin "P2") (pinfunction "D_P2") (pintype "passive"))
      (node (ref "R4") (pin "P$1") (pinfunction "P1_P$1") (pintype "passive"))
    )
    (net (code "40") (name "Net-(J20-P2)") (class "Default")
      (node (ref "J1") (pin "2") (pinfunction "2_2") (pintype "bidirectional"))
      (node (ref "J20") (pin "2") (pinfunction "P2_2") (pintype "passive"))
      (node (ref "Q2") (pin "P2") (pinfunction "D_P2") (pintype "passive"))
    )
    (net (code "41") (name "Net-(LED1-C)") (class "Default")
      (node (ref "LED1") (pin "K") (pinfunction "C_K") (pintype "passive"))
      (node (ref "R4") (pin "P$2") (pinfunction "P2_P$2") (pintype "passive"))
    )
    (net (code "42") (name "Net-(Q1-G)") (class "Default")
      (node (ref "Q1") (pin "P1") (pinfunction "G_P1") (pintype "passive"))
      (node (ref "R2") (pin "P$2") (pinfunction "P2_P$2") (pintype "passive"))
      (node (ref "R3") (pin "P$1") (pinfunction "P1_P$1") (pintype "passive"))
    )
    (net (code "43") (name "Net-(Q2-G)") (class "Default")
      (node (ref "Q2") (pin "P1") (pinfunction "G_P1") (pintype "passive"))
      (node (ref "R7") (pin "P$1") (pinfunction "P1_P$1") (pintype "passive"))
      (node (ref "R8") (pin "P$2") (pinfunction "P2_P$2") (pintype "passive"))
    )
    (net (code "44") (name "Net-(R5-P1)") (class "Default")
      (node (ref "R5") (pin "P$1") (pinfunction "P1_P$1") (pintype "passive"))
      (node (ref "R6") (pin "P$2") (pinfunction "P2_P$2") (pintype "passive"))
      (node (ref "VRG-2") (pin "P1") (pinfunction "ADJ_P1") (pintype "power_in"))
    )
    (net (code "45") (name "Net-(U1-A0)") (class "Default")
      (node (ref "J6") (pin "14") (pinfunction "14_14") (pintype "passive"))
      (node (ref "JP4") (pin "1") (pinfunction "1_1") (pintype "passive"))
      (node (ref "U1") (pin "15") (pinfunction "A0_15") (pintype "input"))
    )
    (net (code "46") (name "Net-(U1-A1)") (class "Default")
      (node (ref "J6") (pin "13") (pinfunction "13_13") (pintype "passive"))
      (node (ref "JP3") (pin "1") (pinfunction "1_1") (pintype "passive"))
      (node (ref "U1") (pin "16") (pinfunction "A1_16") (pintype "input"))
    )
    (net (code "47") (name "Net-(U1-A2)") (class "Default")
      (node (ref "J6") (pin "12") (pinfunction "12_12") (pintype "passive"))
      (node (ref "JP2") (pin "1") (pinfunction "1_1") (pintype "passive"))
      (node (ref "U1") (pin "17") (pinfunction "A2_17") (pintype "input"))
    )
    (net (code "48") (name "Net-(U1-GPB0)") (class "Default")
      (node (ref "J5") (pin "1") (pinfunction "1_1") (pintype "passive"))
      (node (ref "U1") (pin "1") (pinfunction "GPB0_1") (pintype "bidirectional"))
    )
    (net (code "49") (name "Net-(U1-GPB1)") (class "Default")
      (node (ref "J5") (pin "2") (pinfunction "2_2") (pintype "passive"))
      (node (ref "U1") (pin "2") (pinfunction "GPB1_2") (pintype "bidirectional"))
    )
    (net (code "50") (name "Net-(U1-INTA)") (class "Default")
      (node (ref "J6") (pin "9") (pinfunction "9_9") (pintype "passive"))
      (node (ref "U1") (pin "20") (pinfunction "INTA_20") (pintype "output"))
    )
    (net (code "51") (name "Net-(U1-INTB)") (class "Default")
      (node (ref "J6") (pin "10") (pinfunction "10_10") (pintype "passive"))
      (node (ref "U1") (pin "19") (pinfunction "INTB_19") (pintype "output"))
    )
    (net (code "52") (name "Net-(U1-~{RESET})") (class "Default")
      (node (ref "J6") (pin "11") (pinfunction "11_11") (pintype "passive"))
      (node (ref "JP1") (pin "1") (pinfunction "1_1") (pintype "passive"))
      (node (ref "U1") (pin "18") (pinfunction "~{RESET}_18") (pintype "input"))
    )
    (net (code "53") (name "Net-(VRG-1-R.C.)") (class "Default")
      (node (ref "J12") (pin "1") (pinfunction "1_1") (pintype "passive"))
      (node (ref "VRG-1") (pin "P$13") (pinfunction "R.C._P$13") (pintype "input"))
    )
    (net (code "54") (name "Net-(VRG-1-TRIM)") (class "Default")
      (node (ref "J12") (pin "2") (pinfunction "2_2") (pintype "passive"))
      (node (ref "VRG-1") (pin "P$12") (pinfunction "TRIM_P$12") (pintype "output"))
    )
    (net (code "55") (name "SFX-0") (class "Default")
      (node (ref "ASM-2") (pin "2") (pinfunction "0_2") (pintype "input"))
      (node (ref "J6") (pin "7") (pinfunction "7_7") (pintype "passive"))
      (node (ref "J7") (pin "2") (pinfunction "2_2") (pintype "passive"))
      (node (ref "U1") (pin "22") (pinfunction "GPA1_22") (pintype "bidirectional"))
    )
    (net (code "56") (name "SFX-1") (class "Default")
      (node (ref "ASM-2") (pin "3") (pinfunction "1_3") (pintype "input"))
      (node (ref "J6") (pin "6") (pinfunction "6_6") (pintype "passive"))
      (node (ref "J7") (pin "3") (pinfunction "3_3") (pintype "passive"))
      (node (ref "U1") (pin "23") (pinfunction "GPA2_23") (pintype "bidirectional"))
    )
    (net (code "57") (name "SFX-2") (class "Default")
      (node (ref "ASM-2") (pin "4") (pinfunction "2_4") (pintype "input"))
      (node (ref "J6") (pin "5") (pinfunction "5_5") (pintype "passive"))
      (node (ref "J7") (pin "4") (pinfunction "4_4") (pintype "passive"))
      (node (ref "U1") (pin "24") (pinfunction "GPA3_24") (pintype "bidirectional"))
    )
    (net (code "58") (name "SFX-3") (class "Default")
      (node (ref "ASM-2") (pin "5") (pinfunction "3_5") (pintype "input"))
      (node (ref "J6") (pin "4") (pinfunction "4_4") (pintype "passive"))
      (node (ref "J7") (pin "5") (pinfunction "5_5") (pintype "passive"))
      (node (ref "U1") (pin "25") (pinfunction "GPA4_25") (pintype "bidirectional"))
    )
    (net (code "59") (name "SFX-4") (class "Default")
      (node (ref "ASM-2") (pin "6") (pinfunction "4_6") (pintype "input"))
      (node (ref "J6") (pin "3") (pinfunction "3_3") (pintype "passive"))
      (node (ref "J7") (pin "6") (pinfunction "6_6") (pintype "passive"))
      (node (ref "U1") (pin "26") (pinfunction "GPA5_26") (pintype "bidirectional"))
    )
    (net (code "60") (name "SFX-5") (class "Default")
      (node (ref "ASM-2") (pin "7") (pinfunction "5_7") (pintype "input"))
      (node (ref "J6") (pin "2") (pinfunction "2_2") (pintype "passive"))
      (node (ref "J7") (pin "7") (pinfunction "7_7") (pintype "passive"))
      (node (ref "U1") (pin "27") (pinfunction "GPA6_27") (pintype "bidirectional"))
    )
    (net (code "61") (name "SFX-6") (class "Default")
      (node (ref "ASM-2") (pin "8") (pinfunction "6_8") (pintype "input"))
      (node (ref "J6") (pin "1") (pinfunction "1_1") (pintype "passive"))
      (node (ref "J7") (pin "8") (pinfunction "8_8") (pintype "passive"))
      (node (ref "U1") (pin "28") (pinfunction "GPA7_28") (pintype "bidirectional"))
    )
    (net (code "62") (name "SFX-7") (class "Default")
      (node (ref "ASM-2") (pin "9") (pinfunction "7_9") (pintype "input"))
      (node (ref "J5") (pin "8") (pinfunction "8_8") (pintype "passive"))
      (node (ref "J7") (pin "9") (pinfunction "9_9") (pintype "passive"))
      (node (ref "U1") (pin "8") (pinfunction "GPB7_8") (pintype "bidirectional"))
    )
    (net (code "63") (name "SFX-8") (class "Default")
      (node (ref "ASM-2") (pin "10") (pinfunction "8_10") (pintype "input"))
      (node (ref "J5") (pin "7") (pinfunction "7_7") (pintype "passive"))
      (node (ref "J7") (pin "10") (pinfunction "10_10") (pintype "passive"))
      (node (ref "U1") (pin "7") (pinfunction "GPB6_7") (pintype "bidirectional"))
    )
    (net (code "64") (name "SFX-9") (class "Default")
      (node (ref "ASM-2") (pin "11") (pinfunction "9_11") (pintype "input"))
      (node (ref "J5") (pin "6") (pinfunction "6_6") (pintype "passive"))
      (node (ref "J7") (pin "11") (pinfunction "11_11") (pintype "passive"))
      (node (ref "U1") (pin "6") (pinfunction "GPB5_6") (pintype "bidirectional"))
    )
    (net (code "65") (name "SFX-10") (class "Default")
      (node (ref "ASM-2") (pin "12") (pinfunction "10_12") (pintype "input"))
      (node (ref "J5") (pin "5") (pinfunction "5_5") (pintype "passive"))
      (node (ref "J7") (pin "12") (pinfunction "12_12") (pintype "passive"))
      (node (ref "U1") (pin "5") (pinfunction "GPB4_5") (pintype "bidirectional"))
    )
    (net (code "66") (name "SFX-LOUT") (class "Default")
      (node (ref "ASM-2") (pin "16") (pinfunction "L+OUT_16") (pintype "output"))
      (node (ref "ASM-3") (pin "4") (pinfunction "L+IN_4") (pintype "input"))
      (node (ref "J8") (pin "13") (pinfunction "13_13") (pintype "passive"))
      (node (ref "J9") (pin "4") (pinfunction "4_4") (pintype "passive"))
    )
    (net (code "67") (name "SFX-ROUT") (class "Default")
      (node (ref "ASM-2") (pin "17") (pinfunction "R+OUT_17") (pintype "output"))
      (node (ref "ASM-3") (pin "7") (pinfunction "R+IN_7") (pintype "input"))
      (node (ref "J8") (pin "12") (pinfunction "12_12") (pintype "passive"))
      (node (ref "J9") (pin "1") (pinfunction "1_1") (pintype "passive"))
    )
    (net (code "68") (name "SFX-RST") (class "Default")
      (node (ref "ASM-2") (pin "1") (pinfunction "~{RESET}_1") (pintype "input"))
      (node (ref "J6") (pin "8") (pinfunction "8_8") (pintype "passive"))
      (node (ref "J7") (pin "1") (pinfunction "1_1") (pintype "passive"))
      (node (ref "U1") (pin "21") (pinfunction "GPA0_21") (pintype "bidirectional"))
    )
    (net (code "69") (name "SFX-VOL-N") (class "Default")
      (node (ref "ASM-2") (pin "20") (pinfunction "VOL-_20") (pintype "input"))
      (node (ref "J5") (pin "3") (pinfunction "3_3") (pintype "passive"))
      (node (ref "J8") (pin "9") (pinfunction "9_9") (pintype "passive"))
      (node (ref "U1") (pin "3") (pinfunction "GPB2_3") (pintype "bidirectional"))
    )
    (net (code "70") (name "SFX-VOL-P") (class "Default")
      (node (ref "ASM-2") (pin "21") (pinfunction "VOL+_21") (pintype "input"))
      (node (ref "J5") (pin "4") (pinfunction "4_4") (pintype "passive"))
      (node (ref "J8") (pin "8") (pinfunction "8_8") (pintype "passive"))
      (node (ref "U1") (pin "4") (pinfunction "GPB3_4") (pintype "bidirectional"))
    )
    (net (code "71") (name "SPI-MISO") (class "Default")
      (node (ref "ASM-1") (pin "MISO") (pinfunction "MISO_MISO") (pintype "bidirectional"))
      (node (ref "J3") (pin "13") (pinfunction "13_13") (pintype "passive"))
    )
    (net (code "72") (name "SPI-MOSI") (class "Default")
      (node (ref "ASM-1") (pin "MOSI") (pinfunction "MOSI_MOSI") (pintype "bidirectional"))
      (node (ref "J3") (pin "12") (pinfunction "12_12") (pintype "passive"))
    )
    (net (code "73") (name "SPI-SCK") (class "Default")
      (node (ref "ASM-1") (pin "SCK") (pinfunction "SCK_SCK") (pintype "bidirectional"))
      (node (ref "J3") (pin "11") (pinfunction "11_11") (pintype "passive"))
    )
    (net (code "74") (name "VBAT") (class "Default")
      (node (ref "ASM-1") (pin "VBAT") (pinfunction "VBAT_VBAT") (pintype "power_in"))
      (node (ref "J4") (pin "1") (pinfunction "1_1") (pintype "passive"))
    )
    (net (code "75") (name "unconnected-(ASM-2-CS-Pad19)") (class "Default")
      (node (ref "ASM-2") (pin "19") (pinfunction "CS_19") (pintype "no_connect"))
    )
    (net (code "76") (name "unconnected-(ASM-2-PB-Pad25)") (class "Default")
      (node (ref "ASM-2") (pin "25") (pinfunction "PB_25") (pintype "no_connect"))
    )
    (net (code "77") (name "unconnected-(ASM-3-GAIN1-Pad9)") (class "Default")
      (node (ref "ASM-3") (pin "9") (pinfunction "GAIN1_9") (pintype "passive"))
    )
    (net (code "78") (name "unconnected-(ASM-3-GAIN2-Pad8)") (class "Default")
      (node (ref "ASM-3") (pin "8") (pinfunction "GAIN2_8") (pintype "passive"))
    )
    (net (code "79") (name "unconnected-(ASM-3-L+OUT-Pad13)") (class "Default")
      (node (ref "ASM-3") (pin "13") (pinfunction "L+OUT_13") (pintype "output"))
    )
    (net (code "80") (name "unconnected-(ASM-3-L-OUT-Pad12)") (class "Default")
      (node (ref "ASM-3") (pin "12") (pinfunction "L-OUT_12") (pintype "output"))
    )
    (net (code "81") (name "unconnected-(ASM-3-R+OUT-Pad14)") (class "Default")
      (node (ref "ASM-3") (pin "14") (pinfunction "R+OUT_14") (pintype "output"))
    )
    (net (code "82") (name "unconnected-(ASM-3-R-OUT-Pad15)") (class "Default")
      (node (ref "ASM-3") (pin "15") (pinfunction "R-OUT_15") (pintype "output"))
    )
    (net (code "83") (name "unconnected-(J2-Pad1)") (class "Default")
      (node (ref "J2") (pin "1") (pinfunction "1_1") (pintype "bidirectional"))
    )
    (net (code "84") (name "unconnected-(J2-Pad2)") (class "Default")
      (node (ref "J2") (pin "2") (pinfunction "2_2") (pintype "bidirectional"))
    )
    (net (code "85") (name "unconnected-(J2-Pad3)") (class "Default")
      (node (ref "J2") (pin "3") (pinfunction "3_3") (pintype "bidirectional"))
    )
    (net (code "86") (name "unconnected-(J2-Pad4)") (class "Default")
      (node (ref "J2") (pin "4") (pinfunction "4_4") (pintype "bidirectional"))
    )
    (net (code "87") (name "unconnected-(J2-Pad5)") (class "Default")
      (node (ref "J2") (pin "5") (pinfunction "5_5") (pintype "bidirectional"))
    )
    (net (code "88") (name "unconnected-(J2-Pad6)") (class "Default")
      (node (ref "J2") (pin "6") (pinfunction "6_6") (pintype "bidirectional"))
    )
    (net (code "89") (name "unconnected-(J5-Pad11)") (class "Default")
      (node (ref "J5") (pin "11") (pinfunction "11_11") (pintype "passive"))
    )
    (net (code "90") (name "unconnected-(J5-Pad14)") (class "Default")
      (node (ref "J5") (pin "14") (pinfunction "14_14") (pintype "passive"))
    )
    (net (code "91") (name "unconnected-(J8-Pad4)") (class "Default")
      (node (ref "J8") (pin "4") (pinfunction "4_4") (pintype "passive"))
    )
    (net (code "92") (name "unconnected-(J8-Pad10)") (class "Default")
      (node (ref "J8") (pin "10") (pinfunction "10_10") (pintype "passive"))
    )
    (net (code "93") (name "unconnected-(THM-1-K-Pad1)") (class "Default")
      (node (ref "THM-1") (pin "1") (pinfunction "K_1") (pintype "passive"))
    )
    (net (code "94") (name "unconnected-(THM-1-K-Pad2)") (class "Default")
      (node (ref "THM-1") (pin "2") (pinfunction "K_2") (pintype "passive"))
    )
    (net (code "95") (name "unconnected-(THM-2-K-PadP$1)") (class "Default")
      (node (ref "THM-2") (pin "P$1") (pinfunction "K_P$1") (pintype "passive"))
    )
    (net (code "96") (name "unconnected-(U1-NC-Pad11)") (class "Default")
      (node (ref "U1") (pin "11") (pinfunction "NC_11") (pintype "no_connect"))
    )
    (net (code "97") (name "unconnected-(U1-NC-Pad14)") (class "Default")
      (node (ref "U1") (pin "14") (pinfunction "NC_14") (pintype "no_connect"))
    )
    (net (code "98") (name "unconnected-(VRG-1-NC-PadP$11)") (class "Default")
      (node (ref "VRG-1") (pin "P$11") (pinfunction "NC_P$11") (pintype "no_connect"))
    )
    (net (code "99") (name "~{AMP-SHDN}") (class "Default")
      (node (ref "ASM-1") (pin "D10") (pinfunction "D10_D10") (pintype "bidirectional"))
      (node (ref "ASM-3") (pin "3") (pinfunction "~{SHTDWN}_3") (pintype "input"))
      (node (ref "J4") (pin "7") (pinfunction "7_7") (pintype "passive"))
      (node (ref "J9") (pin "5") (pinfunction "5_5") (pintype "passive"))
      (node (ref "R1") (pin "P$2") (pinfunction "P2_P$2") (pintype "passive"))
    )
  )
)
